# FIO_F.net
KiCad netlist of a schematic drawn in EAGLE
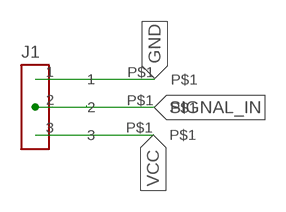
[diagram p0: schematic, sheet 1]

(export (version "E")
  (design (tool "Eeschema 10.0.6"))
  (components
    (comp (ref "J1")
      (value "CONECTOR_FEMEA")
      (footprint "eagle-import:3CONECTOR")
      (libsource (lib "eagle-import") (part "CONECTOR_FEMEA"))
    )
    (comp (ref "U$1")
      (value "PAD")
      (footprint "eagle-import:PAD")
      (libsource (lib "eagle-import") (part "PAD"))
    )
    (comp (ref "U$2")
      (value "PAD")
      (footprint "eagle-import:PAD")
      (libsource (lib "eagle-import") (part "PAD"))
    )
    (comp (ref "VCC")
      (value "PAD")
      (footprint "eagle-import:PAD")
      (libsource (lib "eagle-import") (part "PAD"))
    )
  )
  (nets
    (net (code "1") (name "GND") (class "Default")
      (node (ref "J1") (pin "1") (pinfunction "1_1") (pintype "bidirectional"))
      (node (ref "U$1") (pin "P$1") (pinfunction "P$1_P$1") (pintype "bidirectional"))
    )
    (net (code "2") (name "SIGNAL_IN") (class "Default")
      (node (ref "J1") (pin "2") (pinfunction "2_2") (pintype "bidirectional"))
      (node (ref "U$2") (pin "P$1") (pinfunction "P$1_P$1") (pintype "bidirectional"))
    )
    (net (code "3") (name "VCC") (class "Default")
      (node (ref "J1") (pin "3") (pinfunction "3_3") (pintype "bidirectional"))
      (node (ref "VCC") (pin "P$1") (pinfunction "P$1_P$1") (pintype "bidirectional"))
    )
  )
)
